# Sheet1.net
KiCad netlist of a schematic drawn in Altium Designer
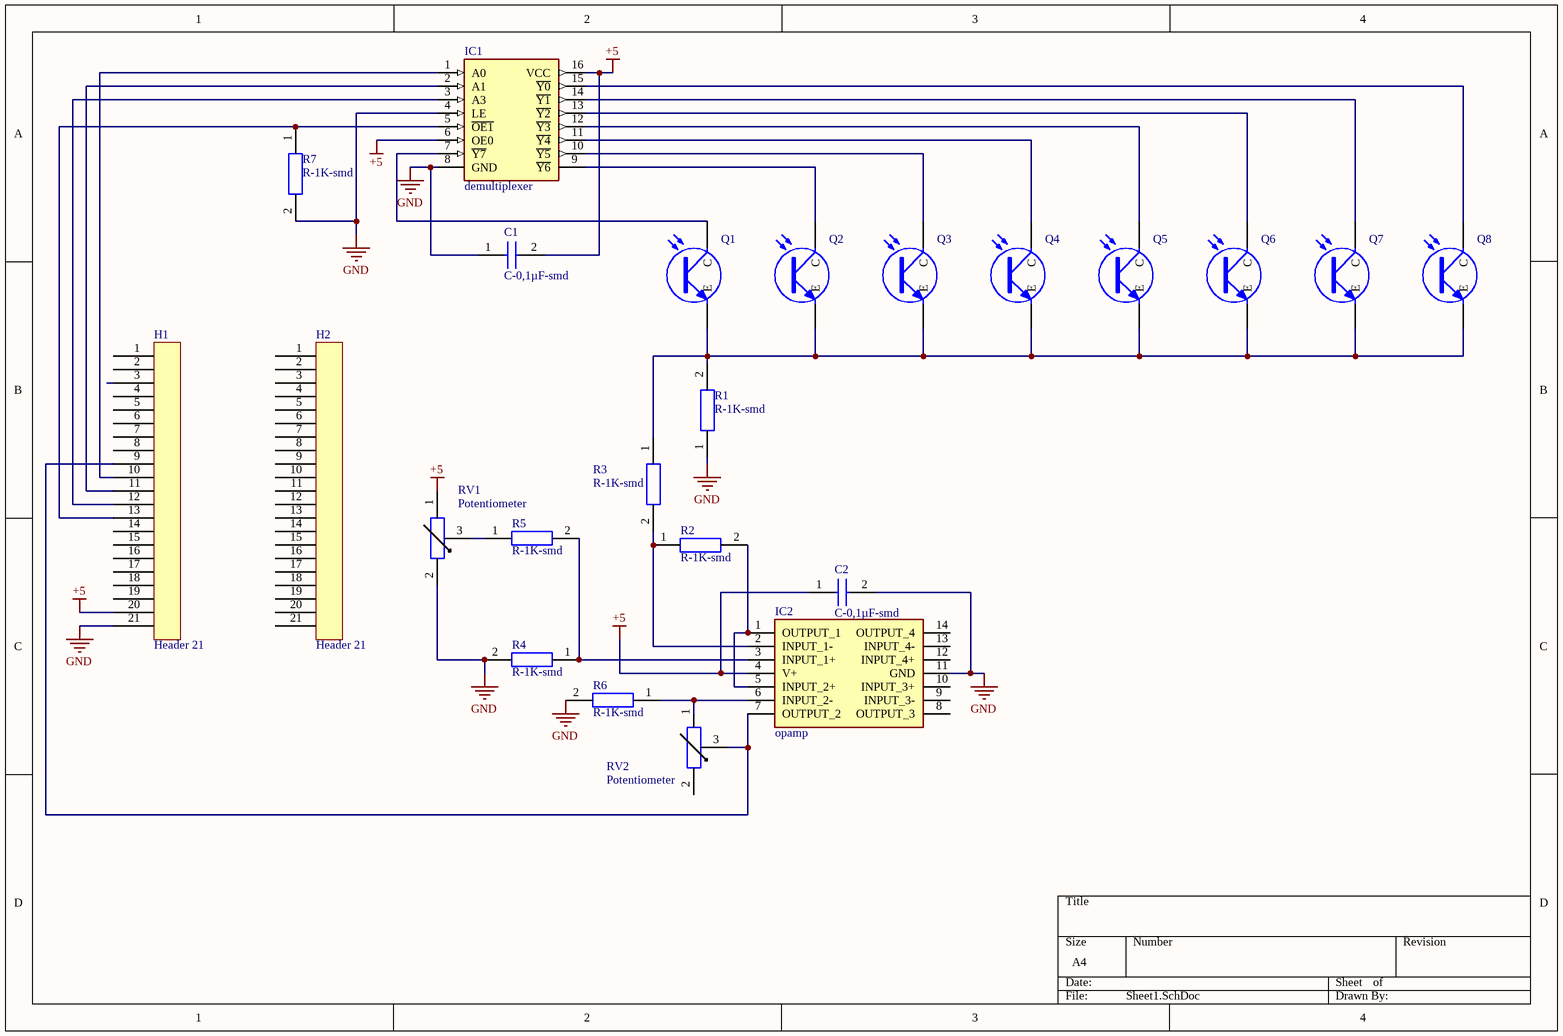
[diagram p0: Sheet1.SchDoc]

(export (version "E")
  (design (tool "Eeschema 10.0.6"))
  (components
    (comp (ref "C1")
      (value "C-0,1µF-smd")
      (footprint "C-0,1µF-smd")
      (description "Capacitor")
      (fields
        (field (name "MOUSER2 PART NUMBER") "80-C0805C104K5RACLR")
        (field (name "MANUFACTURER_PART_NUMBER") "C0805C104K5RAC7411")
      )
      (libsource (lib "Project_Libary") (part "C-0,1µF-smd"))
    )
    (comp (ref "C2")
      (value "C-0,1µF-smd")
      (footprint "C-0,1µF-smd")
      (description "Capacitor")
      (fields
        (field (name "MOUSER2 PART NUMBER") "80-C0805C104K5RACLR")
        (field (name "MANUFACTURER_PART_NUMBER") "C0805C104K5RAC7411")
      )
      (libsource (lib "Project_Libary") (part "C-0,1µF-smd"))
    )
    (comp (ref "H1")
      (value "Header 21")
      (footprint "Header 21")
      (libsource (lib "Project_Libary") (part "Header 21"))
    )
    (comp (ref "H2")
      (value "Header 21")
      (footprint "Header 21")
      (libsource (lib "Project_Libary") (part "Header 21"))
    )
    (comp (ref "IC1")
      (value "demultiplexer")
      (footprint "demultiplexer")
      (description "Integrated Circuit")
      (fields
        (field (name "MOUSER2 PART NUMBER") "595-CD74HC237M")
        (field (name "MANUFACTURER_PART_NUMBER") "CD74HC237M")
      )
      (libsource (lib "Project_Libary") (part "demultiplexer"))
    )
    (comp (ref "IC2")
      (value "opamp")
      (footprint "SOIC127P600X175-14N")
      (description "Integrated Circuit")
      (fields
        (field (name "MOUSER2 PART NUMBER") "926-LM2902MTX/NOPB")
        (field (name "MANUFACTURER_PART_NUMBER") "LM2902MTX/NOPB")
      )
      (libsource (lib "Project_Libary") (part "opamp"))
    )
    (comp (ref "Q1")
      (value "400-1100nm, 1mA, 130deg")
      (footprint "WL-STCW_0805")
      (description "WL-STCW SMT Phototransistor Chip Waterclear, size 0805, 400-1100nm, 1mA, 130deg")
      (fields
        (field (name "MANUFACTURER PART NUMBER") "1540801NBA300")
        (field (name "PUBLISHER") "Wurth Elektronik")
      )
      (libsource (lib "Project_Libary") (part "1540801NBA300"))
    )
    (comp (ref "Q2")
      (value "400-1100nm, 1mA, 130deg")
      (footprint "WL-STCW_0805")
      (description "WL-STCW SMT Phototransistor Chip Waterclear, size 0805, 400-1100nm, 1mA, 130deg")
      (fields
        (field (name "MANUFACTURER PART NUMBER") "1540801NBA300")
        (field (name "PUBLISHER") "Wurth Elektronik")
      )
      (libsource (lib "Project_Libary") (part "1540801NBA300"))
    )
    (comp (ref "Q3")
      (value "400-1100nm, 1mA, 130deg")
      (footprint "WL-STCW_0805")
      (description "WL-STCW SMT Phototransistor Chip Waterclear, size 0805, 400-1100nm, 1mA, 130deg")
      (fields
        (field (name "MANUFACTURER PART NUMBER") "1540801NBA300")
        (field (name "PUBLISHER") "Wurth Elektronik")
      )
      (libsource (lib "Project_Libary") (part "1540801NBA300"))
    )
    (comp (ref "Q4")
      (value "400-1100nm, 1mA, 130deg")
      (footprint "WL-STCW_0805")
      (description "WL-STCW SMT Phototransistor Chip Waterclear, size 0805, 400-1100nm, 1mA, 130deg")
      (fields
        (field (name "MANUFACTURER PART NUMBER") "1540801NBA300")
        (field (name "PUBLISHER") "Wurth Elektronik")
      )
      (libsource (lib "Project_Libary") (part "1540801NBA300"))
    )
    (comp (ref "Q5")
      (value "400-1100nm, 1mA, 130deg")
      (footprint "WL-STCW_0805")
      (description "WL-STCW SMT Phototransistor Chip Waterclear, size 0805, 400-1100nm, 1mA, 130deg")
      (fields
        (field (name "MANUFACTURER PART NUMBER") "1540801NBA300")
        (field (name "PUBLISHER") "Wurth Elektronik")
      )
      (libsource (lib "Project_Libary") (part "1540801NBA300"))
    )
    (comp (ref "Q6")
      (value "400-1100nm, 1mA, 130deg")
      (footprint "WL-STCW_0805")
      (description "WL-STCW SMT Phototransistor Chip Waterclear, size 0805, 400-1100nm, 1mA, 130deg")
      (fields
        (field (name "MANUFACTURER PART NUMBER") "1540801NBA300")
        (field (name "PUBLISHER") "Wurth Elektronik")
      )
      (libsource (lib "Project_Libary") (part "1540801NBA300"))
    )
    (comp (ref "Q7")
      (value "400-1100nm, 1mA, 130deg")
      (footprint "WL-STCW_0805")
      (description "WL-STCW SMT Phototransistor Chip Waterclear, size 0805, 400-1100nm, 1mA, 130deg")
      (fields
        (field (name "MANUFACTURER PART NUMBER") "1540801NBA300")
        (field (name "PUBLISHER") "Wurth Elektronik")
      )
      (libsource (lib "Project_Libary") (part "1540801NBA300"))
    )
    (comp (ref "Q8")
      (value "400-1100nm, 1mA, 130deg")
      (footprint "WL-STCW_0805")
      (description "WL-STCW SMT Phototransistor Chip Waterclear, size 0805, 400-1100nm, 1mA, 130deg")
      (fields
        (field (name "MANUFACTURER PART NUMBER") "1540801NBA300")
        (field (name "PUBLISHER") "Wurth Elektronik")
      )
      (libsource (lib "Project_Libary") (part "1540801NBA300"))
    )
    (comp (ref "R1")
      (value "R-1K-smd")
      (footprint "R-1K-smd")
      (description "Resistor")
      (fields (field (name "MANUFACTURER_PART_NUMBER") "RC0805FR-131KL"))
      (libsource (lib "") (part "R-1K-smd_3"))
    )
    (comp (ref "R2")
      (value "R-1K-smd")
      (footprint "R-1K-smd")
      (description "Resistor")
      (fields (field (name "MANUFACTURER_PART_NUMBER") "RC0805FR-131KL"))
      (libsource (lib "") (part "R-1K-smd_2"))
    )
    (comp (ref "R3")
      (value "R-1K-smd")
      (footprint "R-1K-smd")
      (description "Resistor")
      (fields (field (name "MANUFACTURER_PART_NUMBER") "RC0805FR-131KL"))
      (libsource (lib "Project_Libary") (part "R-1K-smd"))
    )
    (comp (ref "R4")
      (value "R-1K-smd")
      (footprint "R-1K-smd")
      (description "Resistor")
      (fields (field (name "MANUFACTURER_PART_NUMBER") "RC0805FR-131KL"))
      (libsource (lib "") (part "R-1K-smd_1"))
    )
    (comp (ref "R5")
      (value "R-1K-smd")
      (footprint "R-1K-smd")
      (description "Resistor")
      (fields (field (name "MANUFACTURER_PART_NUMBER") "RC0805FR-131KL"))
      (libsource (lib "") (part "R-1K-smd_2"))
    )
    (comp (ref "R6")
      (value "R-1K-smd")
      (footprint "R-1K-smd")
      (description "Resistor")
      (fields (field (name "MANUFACTURER_PART_NUMBER") "RC0805FR-131KL"))
      (libsource (lib "") (part "R-1K-smd_1"))
    )
    (comp (ref "R7")
      (value "R-1K-smd")
      (footprint "R-1K-smd")
      (description "Resistor")
      (fields (field (name "MANUFACTURER_PART_NUMBER") "RC0805FR-131KL"))
      (libsource (lib "Project_Libary") (part "R-1K-smd"))
    )
    (comp (ref "RV1")
      (value "Potentiometer")
      (footprint "Potentiometer")
      (description "PT10LH01-104A2020-S")
      (libsource (lib "Project_Libary") (part "Potentiometer"))
    )
    (comp (ref "RV2")
      (value "Potentiometer")
      (footprint "Potentiometer")
      (description "PT10LH01-104A2020-S")
      (libsource (lib "Project_Libary") (part "Potentiometer"))
    )
  )
  (nets
    (net (code "1") (name "+5") (class "Default")
      (node (ref "C1") (pin "2") (pinfunction "2_2") (pintype "passive"))
      (node (ref "C2") (pin "1") (pinfunction "1_1") (pintype "passive"))
      (node (ref "H1") (pin "20") (pintype "passive"))
      (node (ref "IC1") (pin "16") (pinfunction "VCC_16") (pintype "output"))
      (node (ref "IC1") (pin "6") (pinfunction "OE0_6") (pintype "input"))
      (node (ref "IC2") (pin "4") (pinfunction "V+_4") (pintype "passive"))
      (node (ref "RV1") (pin "1") (pinfunction "1_1") (pintype "passive"))
    )
    (net (code "2") (name "GND") (class "Default")
      (node (ref "C1") (pin "1") (pinfunction "1_1") (pintype "passive"))
      (node (ref "C2") (pin "2") (pinfunction "2_2") (pintype "passive"))
      (node (ref "H1") (pin "21") (pintype "passive"))
      (node (ref "IC1") (pin "4") (pinfunction "LE_4") (pintype "input"))
      (node (ref "IC1") (pin "8") (pinfunction "GND_8") (pintype "power_in"))
      (node (ref "IC2") (pin "11") (pinfunction "GND_11") (pintype "passive"))
      (node (ref "R1") (pin "1") (pinfunction "1_1") (pintype "passive"))
      (node (ref "R4") (pin "2") (pinfunction "2_2") (pintype "passive"))
      (node (ref "R6") (pin "2") (pinfunction "2_2") (pintype "passive"))
      (node (ref "R7") (pin "2") (pinfunction "2_2") (pintype "passive"))
      (node (ref "RV1") (pin "2") (pinfunction "2_2") (pintype "passive"))
    )
    (net (code "3") (name "Net-(IC1-A0)") (class "Default")
      (node (ref "H1") (pin "10") (pintype "passive"))
      (node (ref "IC1") (pin "1") (pinfunction "A0_1") (pintype "input"))
    )
    (net (code "4") (name "Net-(IC1-A1)") (class "Default")
      (node (ref "H1") (pin "11") (pintype "passive"))
      (node (ref "IC1") (pin "2") (pinfunction "A1_2") (pintype "input"))
    )
    (net (code "5") (name "Net-(IC1-A3)") (class "Default")
      (node (ref "H1") (pin "12") (pintype "passive"))
      (node (ref "IC1") (pin "3") (pinfunction "A3_3") (pintype "input"))
    )
    (net (code "6") (name "Net-(IC1-~{OE1})") (class "Default")
      (node (ref "H1") (pin "13") (pintype "passive"))
      (node (ref "IC1") (pin "5") (pinfunction "~{OE1}_5") (pintype "input"))
      (node (ref "R7") (pin "1") (pinfunction "1_1") (pintype "passive"))
    )
    (net (code "7") (name "Net-(IC1-~{Y0})") (class "Default")
      (node (ref "IC1") (pin "15") (pinfunction "~{Y0}_15") (pintype "output"))
      (node (ref "Q8") (pin "1") (pinfunction "C_1") (pintype "passive"))
    )
    (net (code "8") (name "Net-(IC1-~{Y1})") (class "Default")
      (node (ref "IC1") (pin "14") (pinfunction "~{Y1}_14") (pintype "output"))
      (node (ref "Q7") (pin "1") (pinfunction "C_1") (pintype "passive"))
    )
    (net (code "9") (name "Net-(IC1-~{Y2})") (class "Default")
      (node (ref "IC1") (pin "13") (pinfunction "~{Y2}_13") (pintype "output"))
      (node (ref "Q6") (pin "1") (pinfunction "C_1") (pintype "passive"))
    )
    (net (code "10") (name "Net-(IC1-~{Y3})") (class "Default")
      (node (ref "IC1") (pin "12") (pinfunction "~{Y3}_12") (pintype "output"))
      (node (ref "Q5") (pin "1") (pinfunction "C_1") (pintype "passive"))
    )
    (net (code "11") (name "Net-(IC1-~{Y4})") (class "Default")
      (node (ref "IC1") (pin "11") (pinfunction "~{Y4}_11") (pintype "output"))
      (node (ref "Q4") (pin "1") (pinfunction "C_1") (pintype "passive"))
    )
    (net (code "12") (name "Net-(IC1-~{Y5})") (class "Default")
      (node (ref "IC1") (pin "10") (pinfunction "~{Y5}_10") (pintype "output"))
      (node (ref "Q3") (pin "1") (pinfunction "C_1") (pintype "passive"))
    )
    (net (code "13") (name "Net-(IC1-~{Y6})") (class "Default")
      (node (ref "IC1") (pin "9") (pinfunction "~{Y6}_9") (pintype "power_in"))
      (node (ref "Q2") (pin "1") (pinfunction "C_1") (pintype "passive"))
    )
    (net (code "14") (name "Net-(IC1-~{Y7})") (class "Default")
      (node (ref "IC1") (pin "7") (pinfunction "~{Y7}_7") (pintype "input"))
      (node (ref "Q1") (pin "1") (pinfunction "C_1") (pintype "passive"))
    )
    (net (code "15") (name "Net-(IC2-INPUT_1+)") (class "Default")
      (node (ref "IC2") (pin "3") (pinfunction "INPUT_1+_3") (pintype "passive"))
      (node (ref "R4") (pin "1") (pinfunction "1_1") (pintype "passive"))
      (node (ref "R5") (pin "2") (pinfunction "2_2") (pintype "passive"))
    )
    (net (code "16") (name "Net-(IC2-INPUT_1-)") (class "Default")
      (node (ref "IC2") (pin "2") (pinfunction "INPUT_1-_2") (pintype "passive"))
      (node (ref "R2") (pin "1") (pinfunction "1_1") (pintype "passive"))
      (node (ref "R3") (pin "2") (pinfunction "2_2") (pintype "passive"))
    )
    (net (code "17") (name "Net-(IC2-INPUT_2+)") (class "Default")
      (node (ref "IC2") (pin "1") (pinfunction "OUTPUT_1_1") (pintype "passive"))
      (node (ref "IC2") (pin "5") (pinfunction "INPUT_2+_5") (pintype "passive"))
      (node (ref "R2") (pin "2") (pinfunction "2_2") (pintype "passive"))
    )
    (net (code "18") (name "Net-(IC2-INPUT_2-)") (class "Default")
      (node (ref "IC2") (pin "6") (pinfunction "INPUT_2-_6") (pintype "passive"))
      (node (ref "R6") (pin "1") (pinfunction "1_1") (pintype "passive"))
      (node (ref "RV2") (pin "1") (pinfunction "1_1") (pintype "passive"))
    )
    (net (code "19") (name "Net-(IC2-OUTPUT_2)") (class "Default")
      (node (ref "H1") (pin "9") (pintype "passive"))
      (node (ref "IC2") (pin "7") (pinfunction "OUTPUT_2_7") (pintype "passive"))
      (node (ref "RV2") (pin "3") (pinfunction "3_3") (pintype "passive"))
    )
    (net (code "20") (name "Net-(Q1-E)") (class "Default")
      (node (ref "Q1") (pin "2") (pinfunction "E_2") (pintype "passive"))
      (node (ref "Q2") (pin "2") (pinfunction "E_2") (pintype "passive"))
      (node (ref "Q3") (pin "2") (pinfunction "E_2") (pintype "passive"))
      (node (ref "Q4") (pin "2") (pinfunction "E_2") (pintype "passive"))
      (node (ref "Q5") (pin "2") (pinfunction "E_2") (pintype "passive"))
      (node (ref "Q6") (pin "2") (pinfunction "E_2") (pintype "passive"))
      (node (ref "Q7") (pin "2") (pinfunction "E_2") (pintype "passive"))
      (node (ref "Q8") (pin "2") (pinfunction "E_2") (pintype "passive"))
      (node (ref "R1") (pin "2") (pinfunction "2_2") (pintype "passive"))
      (node (ref "R3") (pin "1") (pinfunction "1_1") (pintype "passive"))
    )
    (net (code "21") (name "Net-(R5-Pad1)") (class "Default")
      (node (ref "R5") (pin "1") (pinfunction "1_1") (pintype "passive"))
      (node (ref "RV1") (pin "3") (pinfunction "3_3") (pintype "passive"))
    )
    (net (code "22") (name "unconnected-(H1-Pad1)") (class "Default")
      (node (ref "H1") (pin "1") (pintype "passive"))
    )
    (net (code "23") (name "unconnected-(H1-Pad2)") (class "Default")
      (node (ref "H1") (pin "2") (pintype "passive"))
    )
    (net (code "24") (name "unconnected-(H1-Pad3)") (class "Default")
      (node (ref "H1") (pin "3") (pintype "passive"))
    )
    (net (code "25") (name "unconnected-(H1-Pad4)") (class "Default")
      (node (ref "H1") (pin "4") (pintype "passive"))
    )
    (net (code "26") (name "unconnected-(H1-Pad5)") (class "Default")
      (node (ref "H1") (pin "5") (pintype "passive"))
    )
    (net (code "27") (name "unconnected-(H1-Pad6)") (class "Default")
      (node (ref "H1") (pin "6") (pintype "passive"))
    )
    (net (code "28") (name "unconnected-(H1-Pad7)") (class "Default")
      (node (ref "H1") (pin "7") (pintype "passive"))
    )
    (net (code "29") (name "unconnected-(H1-Pad8)") (class "Default")
      (node (ref "H1") (pin "8") (pintype "passive"))
    )
    (net (code "30") (name "unconnected-(H1-Pad14)") (class "Default")
      (node (ref "H1") (pin "14") (pintype "passive"))
    )
    (net (code "31") (name "unconnected-(H1-Pad15)") (class "Default")
      (node (ref "H1") (pin "15") (pintype "passive"))
    )
    (net (code "32") (name "unconnected-(H1-Pad16)") (class "Default")
      (node (ref "H1") (pin "16") (pintype "passive"))
    )
    (net (code "33") (name "unconnected-(H1-Pad17)") (class "Default")
      (node (ref "H1") (pin "17") (pintype "passive"))
    )
    (net (code "34") (name "unconnected-(H1-Pad18)") (class "Default")
      (node (ref "H1") (pin "18") (pintype "passive"))
    )
    (net (code "35") (name "unconnected-(H1-Pad19)") (class "Default")
      (node (ref "H1") (pin "19") (pintype "passive"))
    )
    (net (code "36") (name "unconnected-(H2-Pad1)") (class "Default")
      (node (ref "H2") (pin "1") (pintype "passive"))
    )
    (net (code "37") (name "unconnected-(H2-Pad2)") (class "Default")
      (node (ref "H2") (pin "2") (pintype "passive"))
    )
    (net (code "38") (name "unconnected-(H2-Pad3)") (class "Default")
      (node (ref "H2") (pin "3") (pintype "passive"))
    )
    (net (code "39") (name "unconnected-(H2-Pad4)") (class "Default")
      (node (ref "H2") (pin "4") (pintype "passive"))
    )
    (net (code "40") (name "unconnected-(H2-Pad5)") (class "Default")
      (node (ref "H2") (pin "5") (pintype "passive"))
    )
    (net (code "41") (name "unconnected-(H2-Pad6)") (class "Default")
      (node (ref "H2") (pin "6") (pintype "passive"))
    )
    (net (code "42") (name "unconnected-(H2-Pad7)") (class "Default")
      (node (ref "H2") (pin "7") (pintype "passive"))
    )
    (net (code "43") (name "unconnected-(H2-Pad8)") (class "Default")
      (node (ref "H2") (pin "8") (pintype "passive"))
    )
    (net (code "44") (name "unconnected-(H2-Pad9)") (class "Default")
      (node (ref "H2") (pin "9") (pintype "passive"))
    )
    (net (code "45") (name "unconnected-(H2-Pad10)") (class "Default")
      (node (ref "H2") (pin "10") (pintype "passive"))
    )
    (net (code "46") (name "unconnected-(H2-Pad11)") (class "Default")
      (node (ref "H2") (pin "11") (pintype "passive"))
    )
    (net (code "47") (name "unconnected-(H2-Pad12)") (class "Default")
      (node (ref "H2") (pin "12") (pintype "passive"))
    )
    (net (code "48") (name "unconnected-(H2-Pad13)") (class "Default")
      (node (ref "H2") (pin "13") (pintype "passive"))
    )
    (net (code "49") (name "unconnected-(H2-Pad14)") (class "Default")
      (node (ref "H2") (pin "14") (pintype "passive"))
    )
    (net (code "50") (name "unconnected-(H2-Pad15)") (class "Default")
      (node (ref "H2") (pin "15") (pintype "passive"))
    )
    (net (code "51") (name "unconnected-(H2-Pad16)") (class "Default")
      (node (ref "H2") (pin "16") (pintype "passive"))
    )
    (net (code "52") (name "unconnected-(H2-Pad17)") (class "Default")
      (node (ref "H2") (pin "17") (pintype "passive"))
    )
    (net (code "53") (name "unconnected-(H2-Pad18)") (class "Default")
      (node (ref "H2") (pin "18") (pintype "passive"))
    )
    (net (code "54") (name "unconnected-(H2-Pad19)") (class "Default")
      (node (ref "H2") (pin "19") (pintype "passive"))
    )
    (net (code "55") (name "unconnected-(H2-Pad20)") (class "Default")
      (node (ref "H2") (pin "20") (pintype "passive"))
    )
    (net (code "56") (name "unconnected-(H2-Pad21)") (class "Default")
      (node (ref "H2") (pin "21") (pintype "passive"))
    )
    (net (code "57") (name "unconnected-(IC2-INPUT_3+-Pad10)") (class "Default")
      (node (ref "IC2") (pin "10") (pinfunction "INPUT_3+_10") (pintype "passive"))
    )
    (net (code "58") (name "unconnected-(IC2-INPUT_3--Pad9)") (class "Default")
      (node (ref "IC2") (pin "9") (pinfunction "INPUT_3-_9") (pintype "passive"))
    )
    (net (code "59") (name "unconnected-(IC2-INPUT_4+-Pad12)") (class "Default")
      (node (ref "IC2") (pin "12") (pinfunction "INPUT_4+_12") (pintype "passive"))
    )
    (net (code "60") (name "unconnected-(IC2-INPUT_4--Pad13)") (class "Default")
      (node (ref "IC2") (pin "13") (pinfunction "INPUT_4-_13") (pintype "passive"))
    )
    (net (code "61") (name "unconnected-(IC2-OUTPUT_3-Pad8)") (class "Default")
      (node (ref "IC2") (pin "8") (pinfunction "OUTPUT_3_8") (pintype "passive"))
    )
    (net (code "62") (name "unconnected-(IC2-OUTPUT_4-Pad14)") (class "Default")
      (node (ref "IC2") (pin "14") (pinfunction "OUTPUT_4_14") (pintype "passive"))
    )
    (net (code "63") (name "unconnected-(RV2-Pad2)") (class "Default")
      (node (ref "RV2") (pin "2") (pinfunction "2_2") (pintype "passive"))
    )
  )
)
